# robot.net
KiCad netlist of a schematic drawn in EAGLE
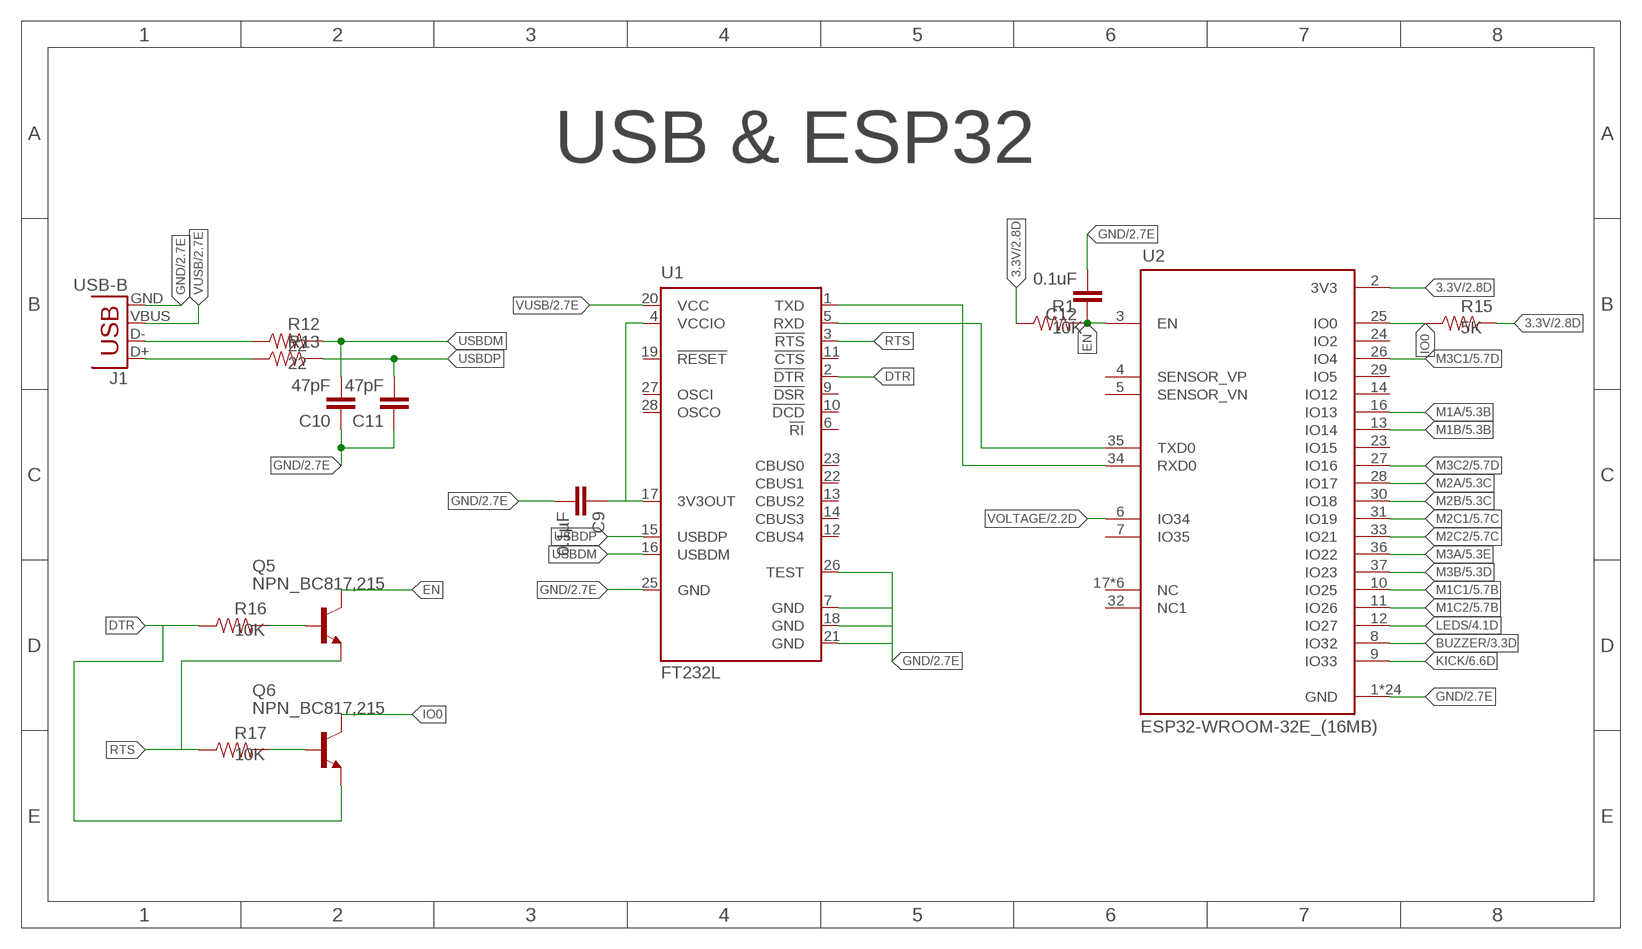
[diagram p0: schematic, sheet 1]
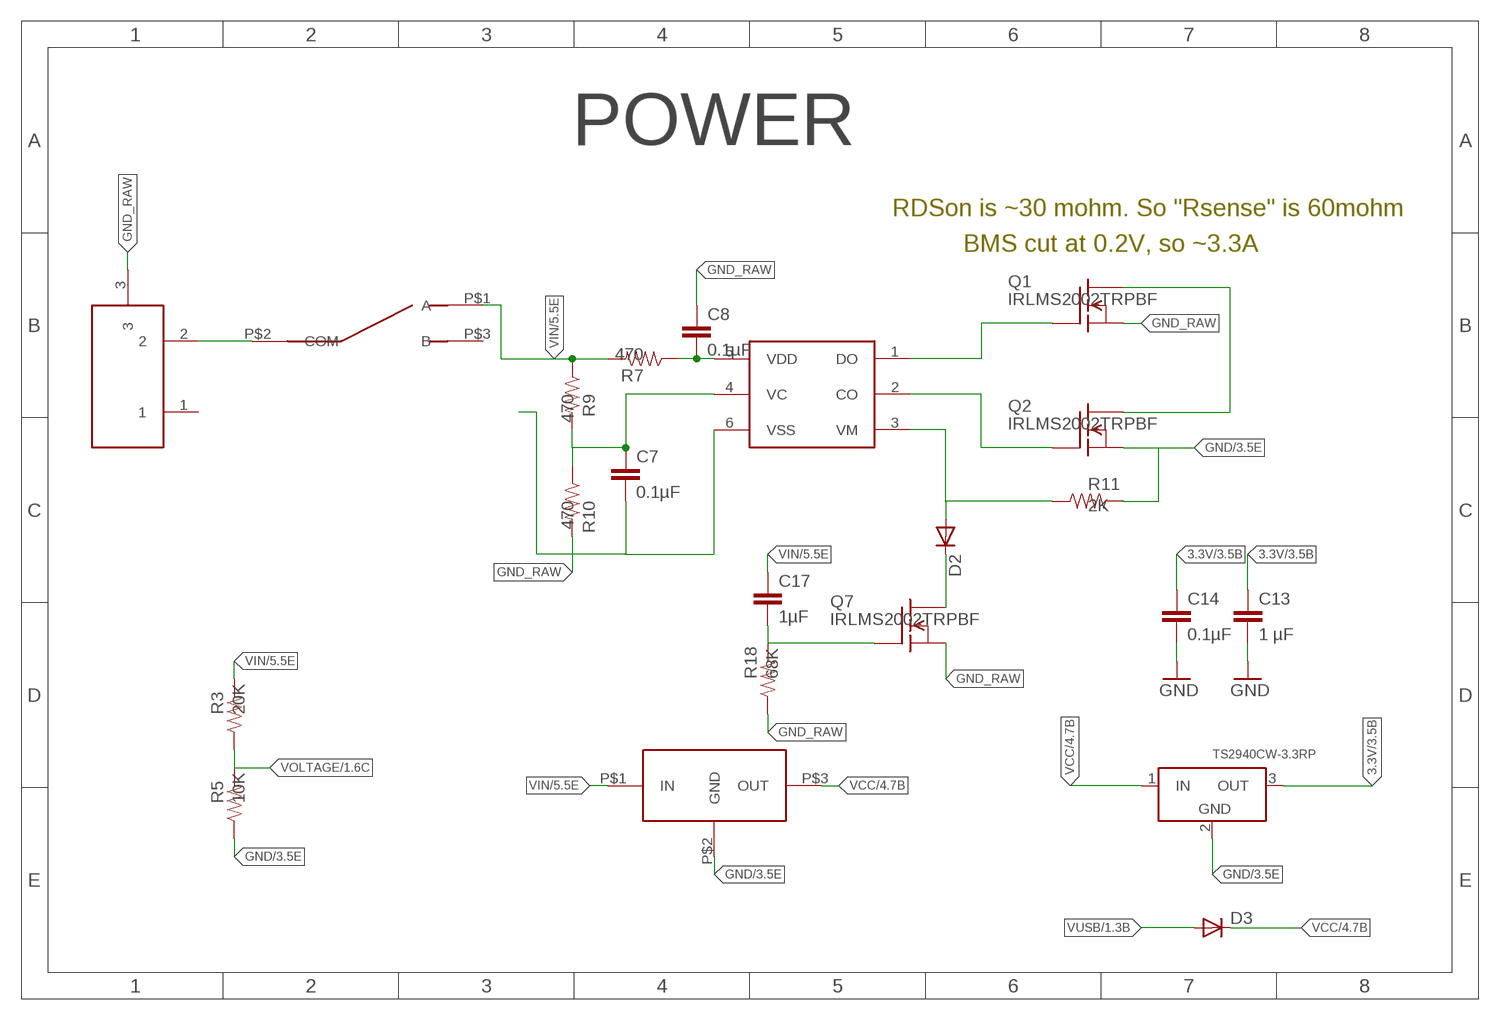
[diagram p1: schematic, sheet 2]
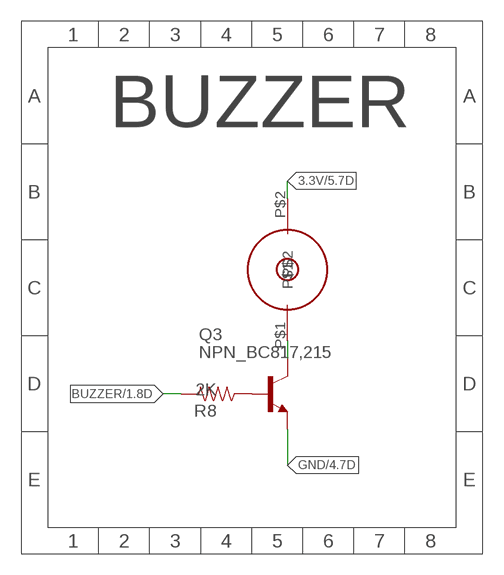
[diagram p2: schematic, sheet 3]
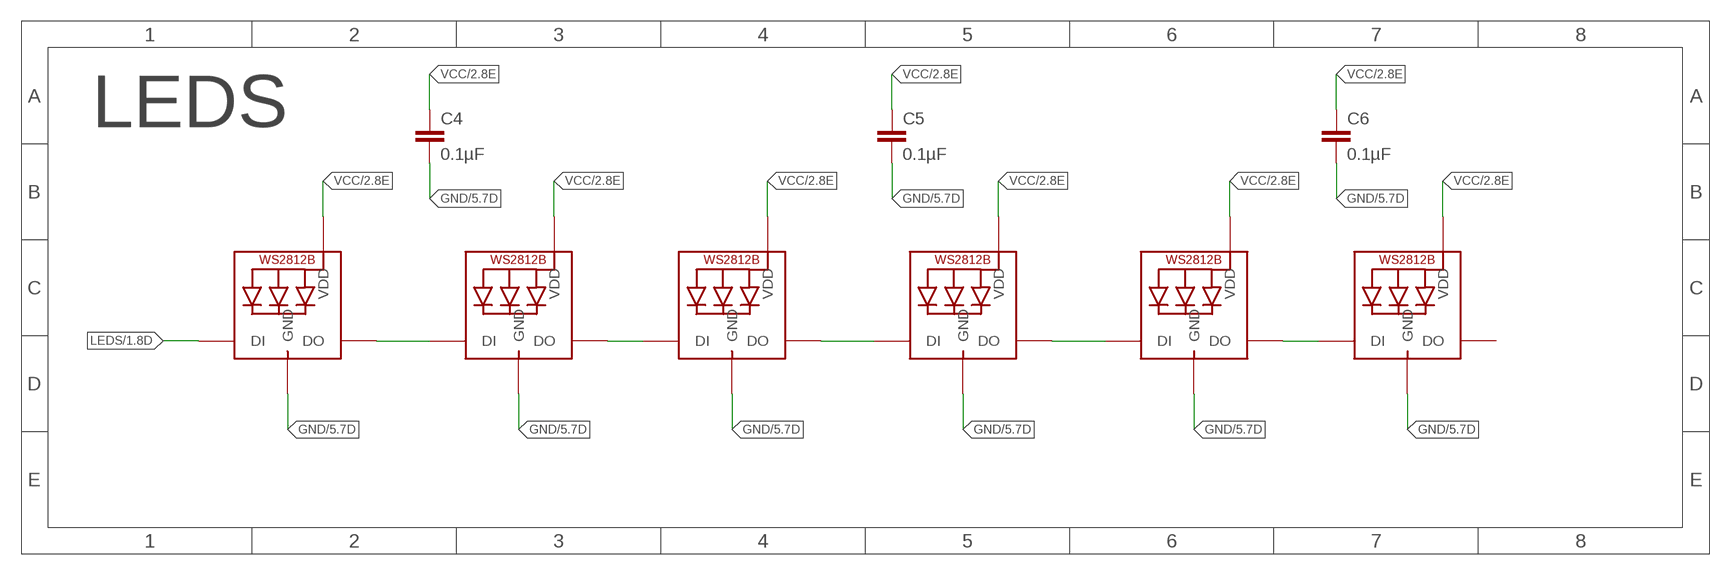
[diagram p3: schematic, sheet 4]
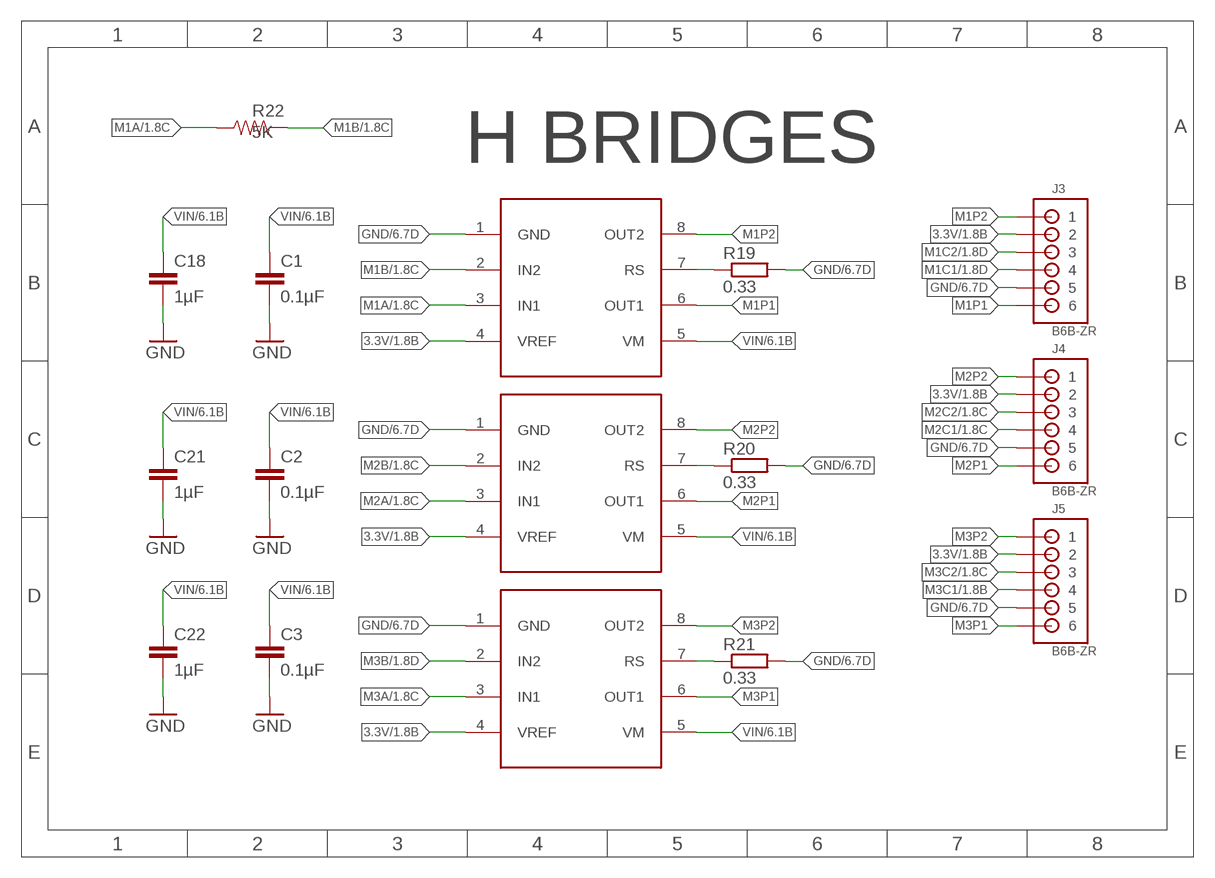
[diagram p4: schematic, sheet 5]
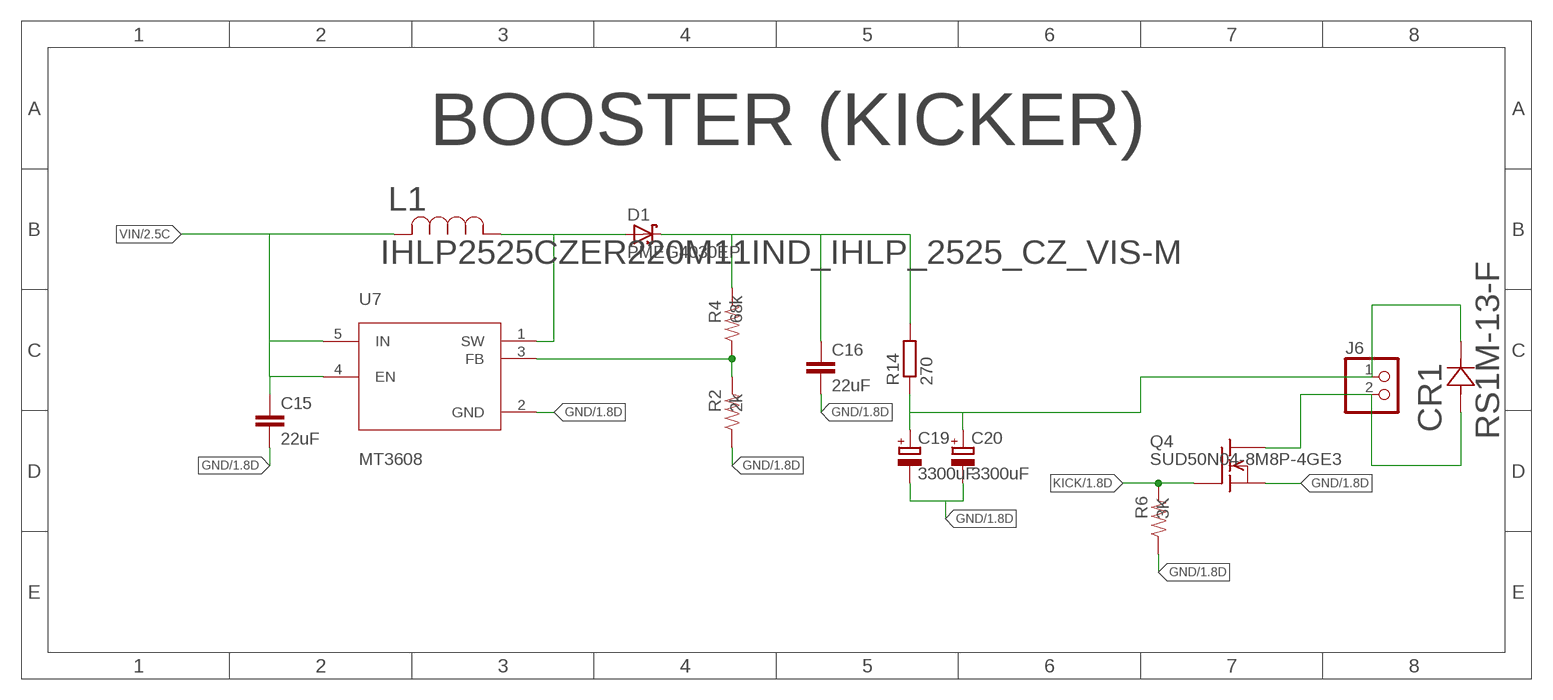
[diagram p5: schematic, sheet 6]

(export (version "E")
  (design (tool "Eeschema 10.0.6"))
  (components
    (comp (ref "C4")
      (value "0.1µF")
      (footprint "eagle-import:0805")
      (libsource (lib "eagle-import") (part "0.33UF/330NF-0805-50V-10%"))
    )
    (comp (ref "C5")
      (value "0.1µF")
      (footprint "eagle-import:0805")
      (fields (field (name "PROD_ID") "CAP-08469"))
      (libsource (lib "eagle-import") (part "0.33UF/330NF-0805-50V-10%"))
    )
    (comp (ref "C6")
      (value "0.1µF")
      (footprint "eagle-import:0805")
      (fields (field (name "PROD_ID") "CAP-08469"))
      (libsource (lib "eagle-import") (part "0.33UF/330NF-0805-50V-10%"))
    )
    (comp (ref "LED1")
      (value "WS2812B5050")
      (footprint "eagle-import:WS2812B")
      (libsource (lib "eagle-import") (part "WS2812B5050"))
    )
    (comp (ref "LED2")
      (value "WS2812B5050")
      (footprint "eagle-import:WS2812B")
      (libsource (lib "eagle-import") (part "WS2812B5050"))
    )
    (comp (ref "LED3")
      (value "WS2812B5050")
      (footprint "eagle-import:WS2812B")
      (libsource (lib "eagle-import") (part "WS2812B5050"))
    )
    (comp (ref "LED4")
      (value "WS2812B5050")
      (footprint "eagle-import:WS2812B")
      (libsource (lib "eagle-import") (part "WS2812B5050"))
    )
    (comp (ref "LED5")
      (value "WS2812B5050")
      (footprint "eagle-import:WS2812B")
      (libsource (lib "eagle-import") (part "WS2812B5050"))
    )
    (comp (ref "LED6")
      (value "WS2812B5050")
      (footprint "eagle-import:WS2812B")
      (libsource (lib "eagle-import") (part "WS2812B5050"))
    )
    (comp (ref "C9")
      (value "0.1µF")
      (footprint "eagle-import:0805")
      (libsource (lib "eagle-import") (part "0.33UF/330NF-0805-50V-10%"))
    )
    (comp (ref "C10")
      (value "47pF")
      (footprint "eagle-import:0805")
      (libsource (lib "eagle-import") (part "CAP0805"))
    )
    (comp (ref "C11")
      (value "47pF")
      (footprint "eagle-import:0805")
      (libsource (lib "eagle-import") (part "CAP0805"))
    )
    (comp (ref "C12")
      (value "0.1uF")
      (footprint "eagle-import:0805")
      (libsource (lib "eagle-import") (part "CAP0805"))
    )
    (comp (ref "J1")
      (value "USB-B")
      (footprint "eagle-import:USB-B-PTH")
      (libsource (lib "eagle-import") (part "USBPTH"))
    )
    (comp (ref "Q5")
      (value "NPN_BC817,215")
      (footprint "eagle-import:SOT-23")
      (libsource (lib "eagle-import") (part "NPN_BC817,215"))
    )
    (comp (ref "Q6")
      (value "NPN_BC817,215")
      (footprint "eagle-import:SOT-23")
      (libsource (lib "eagle-import") (part "NPN_BC817,215"))
    )
    (comp (ref "R1")
      (value "10K")
      (footprint "eagle-import:0805")
      (fields (field (name "PROD_ID") "RES-11622"))
      (libsource (lib "eagle-import") (part "0.3OHM-0805-1/8W-1%"))
    )
    (comp (ref "R12")
      (value "22")
      (footprint "eagle-import:0805")
      (libsource (lib "eagle-import") (part "0.3OHM-0805-1/8W-1%"))
    )
    (comp (ref "R13")
      (value "22")
      (footprint "eagle-import:0805")
      (fields (field (name "PROD_ID") "RES-11622"))
      (libsource (lib "eagle-import") (part "0.3OHM-0805-1/8W-1%"))
    )
    (comp (ref "R15")
      (value "5K")
      (footprint "eagle-import:0805")
      (fields (field (name "PROD_ID") "RES-11622"))
      (libsource (lib "eagle-import") (part "0.3OHM-0805-1/8W-1%"))
    )
    (comp (ref "R16")
      (value "10K")
      (footprint "eagle-import:0805")
      (fields (field (name "PROD_ID") "RES-11622"))
      (libsource (lib "eagle-import") (part "0.3OHM-0805-1/8W-1%"))
    )
    (comp (ref "R17")
      (value "10K")
      (footprint "eagle-import:0805")
      (fields (field (name "PROD_ID") "RES-11622"))
      (libsource (lib "eagle-import") (part "0.3OHM-0805-1/8W-1%"))
    )
    (comp (ref "U1")
      (value "FT232L")
      (footprint "eagle-import:SSOP28")
      (fields (field (name "MPN") "FT232RL"))
      (libsource (lib "eagle-import") (part "FT232L"))
    )
    (comp (ref "U2")
      (value "ESP32-WROOM-32E_(16MB)")
      (footprint "eagle-import:MODULE_ESP32-WROOM-32E_(16MB)")
      (fields (field (name "MF") "Espressif Systems") (field (name "MP") "ESP32-WROOM-32E (16MB)"))
      (libsource (lib "eagle-import") (part "ESP32-WROOM-32E_(16MB)"))
    )
    (comp (ref "C15")
      (value "22uF")
      (footprint "eagle-import:C0805")
      (libsource (lib "eagle-import") (part "C-EUC0805"))
    )
    (comp (ref "C16")
      (value "22uF")
      (footprint "eagle-import:C0805")
      (libsource (lib "eagle-import") (part "C-EUC0805"))
    )
    (comp (ref "C19")
      (value "3300uF")
      (footprint "eagle-import:E5-13")
      (libsource (lib "eagle-import") (part "CPOL-EUE5-13"))
    )
    (comp (ref "C20")
      (value "3300uF")
      (footprint "eagle-import:E5-13")
      (libsource (lib "eagle-import") (part "CPOL-EUE5-13"))
    )
    (comp (ref "CR1")
      (value "RS1M-13-F")
      (footprint "eagle-import:RS1M")
      (libsource (lib "eagle-import") (part "RS1M-13-F"))
    )
    (comp (ref "D1")
      (value "PMEG4030EP")
      (footprint "eagle-import:SOD128")
      (libsource (lib "eagle-import") (part "PMEG4030EP"))
    )
    (comp (ref "J6")
      (value "RHOBAN_KICKER")
      (footprint "eagle-import:RHOBAN_KICKER")
      (libsource (lib "eagle-import") (part "RHOBAN_KICKER"))
    )
    (comp (ref "L1")
      (value "IHLP2525CZER220M11IND_IHLP_2525_CZ_VIS-M")
      (footprint "eagle-import:IND_IHLP_2525_CZ_VIS-M")
      (fields (field (name "MANUFACTURER_PART_NUMBER") "IHLP2525CZER220M11"))
      (libsource (lib "eagle-import") (part "IHLP2525CZER220M11IND_IHLP_2525_CZ_VIS-M"))
    )
    (comp (ref "Q4")
      (value "SUD50N04-8M8P-4GE3")
      (footprint "eagle-import:TO252")
      (libsource (lib "eagle-import") (part "SUD50N04-8M8P-4GE3"))
    )
    (comp (ref "R2")
      (value "2k")
      (footprint "eagle-import:0805")
      (libsource (lib "eagle-import") (part "0.3OHM-0805-1/8W-1%"))
    )
    (comp (ref "R4")
      (value "68k")
      (footprint "eagle-import:0805")
      (libsource (lib "eagle-import") (part "0.3OHM-0805-1/8W-1%"))
    )
    (comp (ref "R6")
      (value "3K")
      (footprint "eagle-import:0805")
      (fields (field (name "PROD_ID") "RES-11622"))
      (libsource (lib "eagle-import") (part "0.3OHM-0805-1/8W-1%"))
    )
    (comp (ref "R14")
      (value "270")
      (footprint "eagle-import:R2010")
      (libsource (lib "eagle-import") (part "R-EU_R2010"))
    )
    (comp (ref "U7")
      (value "MT3608")
      (footprint "eagle-import:SOT95P280X145-6N")
      (fields (field (name "MF") "Aerosemi Technology Co., Ltd"))
      (libsource (lib "eagle-import") (part "MT3608"))
    )
    (comp (ref "C7")
      (value "0.1µF")
      (footprint "eagle-import:0805")
      (libsource (lib "eagle-import") (part "0.33UF/330NF-0805-50V-10%"))
    )
    (comp (ref "C8")
      (value "0.1µF")
      (footprint "eagle-import:0805")
      (fields (field (name "PROD_ID") "CAP-08469"))
      (libsource (lib "eagle-import") (part "0.33UF/330NF-0805-50V-10%"))
    )
    (comp (ref "C13")
      (value "1 µF")
      (footprint "eagle-import:0805")
      (fields (field (name "PROD_ID") "CAP-08469"))
      (libsource (lib "eagle-import") (part "0.33UF/330NF-0805-50V-10%"))
    )
    (comp (ref "C14")
      (value "0.1µF")
      (footprint "eagle-import:0805")
      (fields (field (name "PROD_ID") "CAP-08469"))
      (libsource (lib "eagle-import") (part "0.33UF/330NF-0805-50V-10%"))
    )
    (comp (ref "C17")
      (value "1µF")
      (footprint "eagle-import:0805")
      (fields (field (name "PROD_ID") "CAP-08469"))
      (libsource (lib "eagle-import") (part "0.33UF/330NF-0805-50V-10%"))
    )
    (comp (ref "D2")
      (value "DIODESOD")
      (footprint "eagle-import:SOD-323")
      (libsource (lib "eagle-import") (part "DIODESOD"))
    )
    (comp (ref "D3")
      (value "DIODESOD")
      (footprint "eagle-import:SOD-323")
      (libsource (lib "eagle-import") (part "DIODESOD"))
    )
    (comp (ref "J2")
      (value "DC21MMX")
      (footprint "eagle-import:DC-21MM")
      (libsource (lib "eagle-import") (part "DC21MMX"))
    )
    (comp (ref "Q1")
      (value "IRLMS2002TRPBF")
      (footprint "eagle-import:SOT23-6")
      (libsource (lib "eagle-import") (part "IRLMS2002TRPBF"))
    )
    (comp (ref "Q2")
      (value "IRLMS2002TRPBF")
      (footprint "eagle-import:SOT23-6")
      (libsource (lib "eagle-import") (part "IRLMS2002TRPBF"))
    )
    (comp (ref "Q7")
      (value "IRLMS2002TRPBF")
      (footprint "eagle-import:SOT23-6")
      (libsource (lib "eagle-import") (part "IRLMS2002TRPBF"))
    )
    (comp (ref "R3")
      (value "20K")
      (footprint "eagle-import:0805")
      (libsource (lib "eagle-import") (part "0.3OHM-0805-1/8W-1%"))
    )
    (comp (ref "R5")
      (value "10K")
      (footprint "eagle-import:0805")
      (libsource (lib "eagle-import") (part "0.3OHM-0805-1/8W-1%"))
    )
    (comp (ref "R7")
      (value "470")
      (footprint "eagle-import:0805")
      (libsource (lib "eagle-import") (part "0.3OHM-0805-1/8W-1%"))
    )
    (comp (ref "R9")
      (value "470")
      (footprint "eagle-import:0805")
      (libsource (lib "eagle-import") (part "0.3OHM-0805-1/8W-1%"))
    )
    (comp (ref "R10")
      (value "470")
      (footprint "eagle-import:0805")
      (libsource (lib "eagle-import") (part "0.3OHM-0805-1/8W-1%"))
    )
    (comp (ref "R11")
      (value "2K")
      (footprint "eagle-import:0805")
      (libsource (lib "eagle-import") (part "0.3OHM-0805-1/8W-1%"))
    )
    (comp (ref "R18")
      (value "68K")
      (footprint "eagle-import:0805")
      (fields (field (name "PROD_ID") "RES-11622"))
      (libsource (lib "eagle-import") (part "0.3OHM-0805-1/8W-1%"))
    )
    (comp (ref "REG1")
      (value "REG_5V")
      (footprint "eagle-import:TRACOPOWER")
      (libsource (lib "eagle-import") (part "REG_5V"))
    )
    (comp (ref "SW1")
      (value "L102011ML04Q")
      (footprint "eagle-import:L102011ML04Q")
      (libsource (lib "eagle-import") (part "L102011ML04Q"))
    )
    (comp (ref "U3")
      (value "S8252")
      (footprint "eagle-import:SOT23-6")
      (libsource (lib "eagle-import") (part "S8252"))
    )
    (comp (ref "U8")
      (value "TS2940CW-3.3RP")
      (footprint "eagle-import:SOT223")
      (libsource (lib "eagle-import") (part "TS2940CW-3.3RP"))
    )
    (comp (ref "B1")
      (value "BUZZER66")
      (footprint "eagle-import:BUZZER66")
      (libsource (lib "eagle-import") (part "BUZZER66"))
    )
    (comp (ref "Q3")
      (value "NPN_BC817,215")
      (footprint "eagle-import:SOT-23")
      (libsource (lib "eagle-import") (part "NPN_BC817,215"))
    )
    (comp (ref "R8")
      (value "2K")
      (footprint "eagle-import:0805")
      (libsource (lib "eagle-import") (part "0.3OHM-0805-1/8W-1%"))
    )
    (comp (ref "C1")
      (value "0.1µF")
      (footprint "eagle-import:0805")
      (libsource (lib "eagle-import") (part "0.33UF/330NF-0805-50V-10%"))
    )
    (comp (ref "C2")
      (value "0.1µF")
      (footprint "eagle-import:0805")
      (fields (field (name "PROD_ID") "CAP-08469"))
      (libsource (lib "eagle-import") (part "0.33UF/330NF-0805-50V-10%"))
    )
    (comp (ref "C3")
      (value "0.1µF")
      (footprint "eagle-import:0805")
      (fields (field (name "PROD_ID") "CAP-08469"))
      (libsource (lib "eagle-import") (part "0.33UF/330NF-0805-50V-10%"))
    )
    (comp (ref "C18")
      (value "1µF")
      (footprint "eagle-import:0805")
      (libsource (lib "eagle-import") (part "0.33UF/330NF-0805-50V-10%"))
    )
    (comp (ref "C21")
      (value "1µF")
      (footprint "eagle-import:0805")
      (fields (field (name "PROD_ID") "CAP-08469"))
      (libsource (lib "eagle-import") (part "0.33UF/330NF-0805-50V-10%"))
    )
    (comp (ref "C22")
      (value "1µF")
      (footprint "eagle-import:0805")
      (fields (field (name "PROD_ID") "CAP-08469"))
      (libsource (lib "eagle-import") (part "0.33UF/330NF-0805-50V-10%"))
    )
    (comp (ref "J3")
      (value "B6B-ZR")
      (footprint "eagle-import:B6B-ZR")
      (libsource (lib "eagle-import") (part "B6B-ZR"))
    )
    (comp (ref "J4")
      (value "B6B-ZR")
      (footprint "eagle-import:B6B-ZR")
      (libsource (lib "eagle-import") (part "B6B-ZR"))
    )
    (comp (ref "J5")
      (value "B6B-ZR")
      (footprint "eagle-import:B6B-ZR")
      (libsource (lib "eagle-import") (part "B6B-ZR"))
    )
    (comp (ref "R19")
      (value "0.33")
      (footprint "eagle-import:R1206")
      (libsource (lib "eagle-import") (part "R-EU_R1206"))
    )
    (comp (ref "R20")
      (value "0.33")
      (footprint "eagle-import:R1206")
      (libsource (lib "eagle-import") (part "R-EU_R1206"))
    )
    (comp (ref "R21")
      (value "0.33")
      (footprint "eagle-import:R1206")
      (libsource (lib "eagle-import") (part "R-EU_R1206"))
    )
    (comp (ref "R22")
      (value "5K")
      (footprint "eagle-import:0805")
      (fields (field (name "PROD_ID") "RES-11622"))
      (libsource (lib "eagle-import") (part "0.3OHM-0805-1/8W-1%"))
    )
    (comp (ref "U10")
      (value "TB67H450FNG")
      (footprint "eagle-import:HSOP8")
      (libsource (lib "eagle-import") (part "TB67H450FNG"))
    )
    (comp (ref "U11")
      (value "TB67H450FNG")
      (footprint "eagle-import:HSOP8")
      (libsource (lib "eagle-import") (part "TB67H450FNG"))
    )
    (comp (ref "U12")
      (value "TB67H450FNG")
      (footprint "eagle-import:HSOP8")
      (libsource (lib "eagle-import") (part "TB67H450FNG"))
    )
  )
  (nets
    (net (code "1") (name "1") (class "Default")
      (node (ref "J2") (pin "1") (pinfunction "1_1") (pintype "power_in"))
    )
    (net (code "2") (name "3.3V") (class "Default")
      (node (ref "B1") (pin "P$2") (pinfunction "P$2_P$2") (pintype "bidirectional"))
      (node (ref "C13") (pin "1") (pinfunction "1_1") (pintype "passive"))
      (node (ref "C14") (pin "1") (pinfunction "1_1") (pintype "passive"))
      (node (ref "J3") (pin "2") (pinfunction "2_2") (pintype "bidirectional"))
      (node (ref "J4") (pin "2") (pinfunction "2_2") (pintype "bidirectional"))
      (node (ref "J5") (pin "2") (pinfunction "2_2") (pintype "bidirectional"))
      (node (ref "R1") (pin "1") (pinfunction "1_1") (pintype "passive"))
      (node (ref "R15") (pin "2") (pinfunction "2_2") (pintype "passive"))
      (node (ref "U10") (pin "4") (pinfunction "VREF_4") (pintype "bidirectional"))
      (node (ref "U11") (pin "4") (pinfunction "VREF_4") (pintype "bidirectional"))
      (node (ref "U12") (pin "4") (pinfunction "VREF_4") (pintype "bidirectional"))
      (node (ref "U2") (pin "2") (pinfunction "3V3_2") (pintype "power_in"))
      (node (ref "U8") (pin "3") (pinfunction "OUT_3") (pintype "output"))
    )
    (net (code "3") (name "BUZZER") (class "Default")
      (node (ref "R8") (pin "2") (pinfunction "2_2") (pintype "passive"))
      (node (ref "U2") (pin "8") (pinfunction "IO32_8") (pintype "bidirectional"))
    )
    (net (code "4") (name "DTR") (class "Default")
      (node (ref "Q6") (pin "2") (pinfunction "E_2") (pintype "passive"))
      (node (ref "R16") (pin "1") (pinfunction "1_1") (pintype "passive"))
      (node (ref "U1") (pin "2") (pinfunction "~{DTR}_2") (pintype "output"))
    )
    (net (code "5") (name "EN") (class "Default")
      (node (ref "C12") (pin "1") (pinfunction "1_1") (pintype "passive"))
      (node (ref "Q5") (pin "3") (pinfunction "C_3") (pintype "passive"))
      (node (ref "R1") (pin "2") (pinfunction "2_2") (pintype "passive"))
      (node (ref "U2") (pin "3") (pinfunction "EN_3") (pintype "input"))
    )
    (net (code "6") (name "GND") (class "Default")
      (node (ref "C1") (pin "2") (pinfunction "2_2") (pintype "passive"))
      (node (ref "C10") (pin "1") (pinfunction "1_1") (pintype "passive"))
      (node (ref "C11") (pin "1") (pinfunction "1_1") (pintype "passive"))
      (node (ref "C12") (pin "2") (pinfunction "2_2") (pintype "passive"))
      (node (ref "C13") (pin "2") (pinfunction "2_2") (pintype "passive"))
      (node (ref "C14") (pin "2") (pinfunction "2_2") (pintype "passive"))
      (node (ref "C15") (pin "2") (pinfunction "2_2") (pintype "passive"))
      (node (ref "C16") (pin "2") (pinfunction "2_2") (pintype "passive"))
      (node (ref "C18") (pin "2") (pinfunction "2_2") (pintype "passive"))
      (node (ref "C19") (pin "-") (pinfunction "-_-") (pintype "passive"))
      (node (ref "C2") (pin "2") (pinfunction "2_2") (pintype "passive"))
      (node (ref "C20") (pin "-") (pinfunction "-_-") (pintype "passive"))
      (node (ref "C21") (pin "2") (pinfunction "2_2") (pintype "passive"))
      (node (ref "C22") (pin "2") (pinfunction "2_2") (pintype "passive"))
      (node (ref "C3") (pin "2") (pinfunction "2_2") (pintype "passive"))
      (node (ref "C4") (pin "2") (pinfunction "2_2") (pintype "passive"))
      (node (ref "C5") (pin "2") (pinfunction "2_2") (pintype "passive"))
      (node (ref "C6") (pin "2") (pinfunction "2_2") (pintype "passive"))
      (node (ref "C9") (pin "2") (pinfunction "2_2") (pintype "passive"))
      (node (ref "J1") (pin "GND") (pinfunction "GND_GND") (pintype "bidirectional"))
      (node (ref "J3") (pin "5") (pinfunction "5_5") (pintype "bidirectional"))
      (node (ref "J4") (pin "5") (pinfunction "5_5") (pintype "bidirectional"))
      (node (ref "J5") (pin "5") (pinfunction "5_5") (pintype "bidirectional"))
      (node (ref "LED1") (pin "3-GND") (pinfunction "GND_3-GND") (pintype "power_in"))
      (node (ref "LED2") (pin "3-GND") (pinfunction "GND_3-GND") (pintype "power_in"))
      (node (ref "LED3") (pin "3-GND") (pinfunction "GND_3-GND") (pintype "power_in"))
      (node (ref "LED4") (pin "3-GND") (pinfunction "GND_3-GND") (pintype "power_in"))
      (node (ref "LED5") (pin "3-GND") (pinfunction "GND_3-GND") (pintype "power_in"))
      (node (ref "LED6") (pin "3-GND") (pinfunction "GND_3-GND") (pintype "power_in"))
      (node (ref "Q2") (pin "4") (pinfunction "S_4") (pintype "passive"))
      (node (ref "Q3") (pin "2") (pinfunction "E_2") (pintype "passive"))
      (node (ref "Q4") (pin "2") (pinfunction "S_2") (pintype "passive"))
      (node (ref "R11") (pin "2") (pinfunction "2_2") (pintype "passive"))
      (node (ref "R19") (pin "2") (pinfunction "2_2") (pintype "passive"))
      (node (ref "R2") (pin "1") (pinfunction "1_1") (pintype "passive"))
      (node (ref "R20") (pin "2") (pinfunction "2_2") (pintype "passive"))
      (node (ref "R21") (pin "2") (pinfunction "2_2") (pintype "passive"))
      (node (ref "R5") (pin "1") (pinfunction "1_1") (pintype "passive"))
      (node (ref "R6") (pin "1") (pinfunction "1_1") (pintype "passive"))
      (node (ref "REG1") (pin "P$2") (pinfunction "GND_P$2") (pintype "bidirectional"))
      (node (ref "U1") (pin "18") (pinfunction "GND_18") (pintype "power_in"))
      (node (ref "U1") (pin "21") (pinfunction "GND_21") (pintype "power_in"))
      (node (ref "U1") (pin "25") (pinfunction "GND_25") (pintype "power_in"))
      (node (ref "U1") (pin "26") (pinfunction "TEST_26") (pintype "input"))
      (node (ref "U1") (pin "7") (pinfunction "GND_7") (pintype "power_in"))
      (node (ref "U10") (pin "1") (pinfunction "GND_1") (pintype "bidirectional"))
      (node (ref "U11") (pin "1") (pinfunction "GND_1") (pintype "bidirectional"))
      (node (ref "U12") (pin "1") (pinfunction "GND_1") (pintype "bidirectional"))
      (node (ref "U2") (pin "1") (pinfunction "GND_1") (pintype "power_in"))
      (node (ref "U2") (pin "15") (pinfunction "GND_15") (pintype "power_in"))
      (node (ref "U2") (pin "38") (pinfunction "GND_38") (pintype "power_in"))
      (node (ref "U2") (pin "39_1") (pinfunction "GND_39_1") (pintype "power_in"))
      (node (ref "U2") (pin "39_10") (pinfunction "GND_39_10") (pintype "power_in"))
      (node (ref "U2") (pin "39_11") (pinfunction "GND_39_11") (pintype "power_in"))
      (node (ref "U2") (pin "39_12") (pinfunction "GND_39_12") (pintype "power_in"))
      (node (ref "U2") (pin "39_13") (pinfunction "GND_39_13") (pintype "power_in"))
      (node (ref "U2") (pin "39_14") (pinfunction "GND_39_14") (pintype "power_in"))
      (node (ref "U2") (pin "39_15") (pinfunction "GND_39_15") (pintype "power_in"))
      (node (ref "U2") (pin "39_16") (pinfunction "GND_39_16") (pintype "power_in"))
      (node (ref "U2") (pin "39_17") (pinfunction "GND_39_17") (pintype "power_in"))
      (node (ref "U2") (pin "39_18") (pinfunction "GND_39_18") (pintype "power_in"))
      (node (ref "U2") (pin "39_19") (pinfunction "GND_39_19") (pintype "power_in"))
      (node (ref "U2") (pin "39_2") (pinfunction "GND_39_2") (pintype "power_in"))
      (node (ref "U2") (pin "39_20") (pinfunction "GND_39_20") (pintype "power_in"))
      (node (ref "U2") (pin "39_21") (pinfunction "GND_39_21") (pintype "power_in"))
      (node (ref "U2") (pin "39_3") (pinfunction "GND_39_3") (pintype "power_in"))
      (node (ref "U2") (pin "39_4") (pinfunction "GND_39_4") (pintype "power_in"))
      (node (ref "U2") (pin "39_5") (pinfunction "GND_39_5") (pintype "power_in"))
      (node (ref "U2") (pin "39_6") (pinfunction "GND_39_6") (pintype "power_in"))
      (node (ref "U2") (pin "39_7") (pinfunction "GND_39_7") (pintype "power_in"))
      (node (ref "U2") (pin "39_8") (pinfunction "GND_39_8") (pintype "power_in"))
      (node (ref "U2") (pin "39_9") (pinfunction "GND_39_9") (pintype "power_in"))
      (node (ref "U7") (pin "2") (pinfunction "GND_2") (pintype "power_in"))
      (node (ref "U8") (pin "2") (pinfunction "GND_2") (pintype "power_in"))
    )
    (net (code "7") (name "GND_RAW") (class "Default")
      (node (ref "C7") (pin "2") (pinfunction "2_2") (pintype "passive"))
      (node (ref "C8") (pin "1") (pinfunction "1_1") (pintype "passive"))
      (node (ref "J2") (pin "3") (pinfunction "3_3") (pintype "power_in"))
      (node (ref "Q1") (pin "4") (pinfunction "S_4") (pintype "passive"))
      (node (ref "Q7") (pin "4") (pinfunction "S_4") (pintype "passive"))
      (node (ref "R10") (pin "2") (pinfunction "2_2") (pintype "passive"))
      (node (ref "R18") (pin "1") (pinfunction "1_1") (pintype "passive"))
      (node (ref "U3") (pin "6") (pinfunction "VSS_6") (pintype "passive"))
    )
    (net (code "8") (name "IO0") (class "Default")
      (node (ref "Q6") (pin "3") (pinfunction "C_3") (pintype "passive"))
      (node (ref "R15") (pin "1") (pinfunction "1_1") (pintype "passive"))
      (node (ref "U2") (pin "25") (pinfunction "IO0_25") (pintype "bidirectional"))
    )
    (net (code "9") (name "KICK") (class "Default")
      (node (ref "Q4") (pin "1") (pinfunction "G_1") (pintype "passive"))
      (node (ref "R6") (pin "2") (pinfunction "2_2") (pintype "passive"))
      (node (ref "U2") (pin "9") (pinfunction "IO33_9") (pintype "bidirectional"))
    )
    (net (code "10") (name "LEDS") (class "Default")
      (node (ref "LED1") (pin "4-DIN") (pinfunction "DI_4-DIN") (pintype "input"))
      (node (ref "U2") (pin "12") (pinfunction "IO27_12") (pintype "bidirectional"))
    )
    (net (code "11") (name "M1A") (class "Default")
      (node (ref "R22") (pin "1") (pinfunction "1_1") (pintype "passive"))
      (node (ref "U10") (pin "3") (pinfunction "IN1_3") (pintype "bidirectional"))
      (node (ref "U2") (pin "16") (pinfunction "IO13_16") (pintype "bidirectional"))
    )
    (net (code "12") (name "M1B") (class "Default")
      (node (ref "R22") (pin "2") (pinfunction "2_2") (pintype "passive"))
      (node (ref "U10") (pin "2") (pinfunction "IN2_2") (pintype "bidirectional"))
      (node (ref "U2") (pin "13") (pinfunction "IO14_13") (pintype "bidirectional"))
    )
    (net (code "13") (name "M1C1") (class "Default")
      (node (ref "J3") (pin "4") (pinfunction "4_4") (pintype "bidirectional"))
      (node (ref "U2") (pin "10") (pinfunction "IO25_10") (pintype "bidirectional"))
    )
    (net (code "14") (name "M1C2") (class "Default")
      (node (ref "J3") (pin "3") (pinfunction "3_3") (pintype "bidirectional"))
      (node (ref "U2") (pin "11") (pinfunction "IO26_11") (pintype "bidirectional"))
    )
    (net (code "15") (name "M1P1") (class "Default")
      (node (ref "J3") (pin "6") (pinfunction "6_6") (pintype "bidirectional"))
      (node (ref "U10") (pin "6") (pinfunction "OUT1_6") (pintype "bidirectional"))
    )
    (net (code "16") (name "M1P2") (class "Default")
      (node (ref "J3") (pin "1") (pinfunction "1_1") (pintype "bidirectional"))
      (node (ref "U10") (pin "8") (pinfunction "OUT2_8") (pintype "bidirectional"))
    )
    (net (code "17") (name "M2A") (class "Default")
      (node (ref "U11") (pin "3") (pinfunction "IN1_3") (pintype "bidirectional"))
      (node (ref "U2") (pin "28") (pinfunction "IO17_28") (pintype "bidirectional"))
    )
    (net (code "18") (name "M2B") (class "Default")
      (node (ref "U11") (pin "2") (pinfunction "IN2_2") (pintype "bidirectional"))
      (node (ref "U2") (pin "30") (pinfunction "IO18_30") (pintype "bidirectional"))
    )
    (net (code "19") (name "M2C1") (class "Default")
      (node (ref "J4") (pin "4") (pinfunction "4_4") (pintype "bidirectional"))
      (node (ref "U2") (pin "31") (pinfunction "IO19_31") (pintype "bidirectional"))
    )
    (net (code "20") (name "M2C2") (class "Default")
      (node (ref "J4") (pin "3") (pinfunction "3_3") (pintype "bidirectional"))
      (node (ref "U2") (pin "33") (pinfunction "IO21_33") (pintype "bidirectional"))
    )
    (net (code "21") (name "M2P1") (class "Default")
      (node (ref "J4") (pin "6") (pinfunction "6_6") (pintype "bidirectional"))
      (node (ref "U11") (pin "6") (pinfunction "OUT1_6") (pintype "bidirectional"))
    )
    (net (code "22") (name "M2P2") (class "Default")
      (node (ref "J4") (pin "1") (pinfunction "1_1") (pintype "bidirectional"))
      (node (ref "U11") (pin "8") (pinfunction "OUT2_8") (pintype "bidirectional"))
    )
    (net (code "23") (name "M3A") (class "Default")
      (node (ref "U12") (pin "3") (pinfunction "IN1_3") (pintype "bidirectional"))
      (node (ref "U2") (pin "36") (pinfunction "IO22_36") (pintype "bidirectional"))
    )
    (net (code "24") (name "M3B") (class "Default")
      (node (ref "U12") (pin "2") (pinfunction "IN2_2") (pintype "bidirectional"))
      (node (ref "U2") (pin "37") (pinfunction "IO23_37") (pintype "bidirectional"))
    )
    (net (code "25") (name "M3C1") (class "Default")
      (node (ref "J5") (pin "4") (pinfunction "4_4") (pintype "bidirectional"))
      (node (ref "U2") (pin "26") (pinfunction "IO4_26") (pintype "bidirectional"))
    )
    (net (code "26") (name "M3C2") (class "Default")
      (node (ref "J5") (pin "3") (pinfunction "3_3") (pintype "bidirectional"))
      (node (ref "U2") (pin "27") (pinfunction "IO16_27") (pintype "bidirectional"))
    )
    (net (code "27") (name "M3P1") (class "Default")
      (node (ref "J5") (pin "6") (pinfunction "6_6") (pintype "bidirectional"))
      (node (ref "U12") (pin "6") (pinfunction "OUT1_6") (pintype "bidirectional"))
    )
    (net (code "28") (name "M3P2") (class "Default")
      (node (ref "J5") (pin "1") (pinfunction "1_1") (pintype "bidirectional"))
      (node (ref "U12") (pin "8") (pinfunction "OUT2_8") (pintype "bidirectional"))
    )
    (net (code "29") (name "Net-(C19-Pad+)") (class "Default")
      (node (ref "C19") (pin "+") (pinfunction "+_+") (pintype "passive"))
      (node (ref "C20") (pin "+") (pinfunction "+_+") (pintype "passive"))
      (node (ref "CR1") (pin "K") (pinfunction "K_K") (pintype "passive"))
      (node (ref "J6") (pin "1") (pinfunction "1_1") (pintype "passive"))
      (node (ref "R14") (pin "1") (pinfunction "1_1") (pintype "passive"))
    )
    (net (code "30") (name "Net-(D1-A)") (class "Default")
      (node (ref "D1") (pin "2") (pinfunction "A_2") (pintype "passive"))
      (node (ref "L1") (pin "1") (pinfunction "1_1") (pintype "passive"))
      (node (ref "U7") (pin "1") (pinfunction "SW_1") (pintype "output"))
    )
    (net (code "31") (name "Net-(D1-K)") (class "Default")
      (node (ref "C16") (pin "1") (pinfunction "1_1") (pintype "passive"))
      (node (ref "D1") (pin "1") (pinfunction "K_1") (pintype "passive"))
      (node (ref "R14") (pin "2") (pinfunction "2_2") (pintype "passive"))
      (node (ref "R4") (pin "2") (pinfunction "2_2") (pintype "passive"))
    )
    (net (code "32") (name "Net-(D2-A)") (class "Default")
      (node (ref "D2") (pin "2") (pinfunction "A_2") (pintype "passive"))
      (node (ref "R11") (pin "1") (pinfunction "1_1") (pintype "passive"))
      (node (ref "U3") (pin "3") (pinfunction "VM_3") (pintype "passive"))
    )
    (net (code "33") (name "Net-(D2-C)") (class "Default")
      (node (ref "D2") (pin "1") (pinfunction "C_1") (pintype "passive"))
      (node (ref "Q7") (pin "1") (pinfunction "D_1") (pintype "passive"))
      (node (ref "Q7") (pin "2") (pinfunction "D_2") (pintype "passive"))
      (node (ref "Q7") (pin "5") (pinfunction "D_5") (pintype "passive"))
      (node (ref "Q7") (pin "6") (pinfunction "D_6") (pintype "passive"))
    )
    (net (code "34") (name "Net-(J1-PadD+)") (class "Default")
      (node (ref "J1") (pin "D+") (pinfunction "D+_D+") (pintype "bidirectional"))
      (node (ref "R13") (pin "1") (pinfunction "1_1") (pintype "passive"))
    )
    (net (code "35") (name "Net-(J1-PadD-)") (class "Default")
      (node (ref "J1") (pin "D-") (pinfunction "D-_D-") (pintype "bidirectional"))
      (node (ref "R12") (pin "1") (pinfunction "1_1") (pintype "passive"))
    )
    (net (code "36") (name "Net-(LED1-DO)") (class "Default")
      (node (ref "LED1") (pin "2-DOUT") (pinfunction "DO_2-DOUT") (pintype "output"))
      (node (ref "LED2") (pin "4-DIN") (pinfunction "DI_4-DIN") (pintype "input"))
    )
    (net (code "37") (name "Net-(LED2-DO)") (class "Default")
      (node (ref "LED2") (pin "2-DOUT") (pinfunction "DO_2-DOUT") (pintype "output"))
      (node (ref "LED3") (pin "4-DIN") (pinfunction "DI_4-DIN") (pintype "input"))
    )
    (net (code "38") (name "Net-(LED3-DO)") (class "Default")
      (node (ref "LED3") (pin "2-DOUT") (pinfunction "DO_2-DOUT") (pintype "output"))
      (node (ref "LED4") (pin "4-DIN") (pinfunction "DI_4-DIN") (pintype "input"))
    )
    (net (code "39") (name "Net-(LED4-DO)") (class "Default")
      (node (ref "LED4") (pin "2-DOUT") (pinfunction "DO_2-DOUT") (pintype "output"))
      (node (ref "LED5") (pin "4-DIN") (pinfunction "DI_4-DIN") (pintype "input"))
    )
    (net (code "40") (name "Net-(LED5-DO)") (class "Default")
      (node (ref "LED5") (pin "2-DOUT") (pinfunction "DO_2-DOUT") (pintype "output"))
      (node (ref "LED6") (pin "4-DIN") (pinfunction "DI_4-DIN") (pintype "input"))
    )
    (net (code "41") (name "Net-(Q1-D-Pad1)") (class "Default")
      (node (ref "Q1") (pin "1") (pinfunction "D_1") (pintype "passive"))
      (node (ref "Q1") (pin "2") (pinfunction "D_2") (pintype "passive"))
      (node (ref "Q1") (pin "5") (pinfunction "D_5") (pintype "passive"))
      (node (ref "Q1") (pin "6") (pinfunction "D_6") (pintype "passive"))
      (node (ref "Q2") (pin "1") (pinfunction "D_1") (pintype "passive"))
      (node (ref "Q2") (pin "2") (pinfunction "D_2") (pintype "passive"))
      (node (ref "Q2") (pin "5") (pinfunction "D_5") (pintype "passive"))
      (node (ref "Q2") (pin "6") (pinfunction "D_6") (pintype "passive"))
    )
    (net (code "42") (name "Net-(Q1-G)") (class "Default")
      (node (ref "Q1") (pin "3") (pinfunction "G_3") (pintype "passive"))
      (node (ref "U3") (pin "1") (pinfunction "DO_1") (pintype "passive"))
    )
    (net (code "43") (name "Net-(Q2-G)") (class "Default")
      (node (ref "Q2") (pin "3") (pinfunction "G_3") (pintype "passive"))
      (node (ref "U3") (pin "2") (pinfunction "CO_2") (pintype "passive"))
    )
    (net (code "44") (name "Net-(Q3-B)") (class "Default")
      (node (ref "Q3") (pin "1") (pinfunction "B_1") (pintype "passive"))
      (node (ref "R8") (pin "1") (pinfunction "1_1") (pintype "passive"))
    )
    (net (code "45") (name "Net-(Q3-C)") (class "Default")
      (node (ref "B1") (pin "P$1") (pinfunction "P$1_P$1") (pintype "bidirectional"))
      (node (ref "Q3") (pin "3") (pinfunction "C_3") (pintype "passive"))
    )
    (net (code "46") (name "Net-(Q4-D)") (class "Default")
      (node (ref "CR1") (pin "A") (pinfunction "A_A") (pintype "passive"))
      (node (ref "J6") (pin "2") (pinfunction "2_2") (pintype "passive"))
      (node (ref "Q4") (pin "3") (pinfunction "D_3") (pintype "passive"))
    )
    (net (code "47") (name "Net-(Q5-B)") (class "Default")
      (node (ref "Q5") (pin "1") (pinfunction "B_1") (pintype "passive"))
      (node (ref "R16") (pin "2") (pinfunction "2_2") (pintype "passive"))
    )
    (net (code "48") (name "Net-(Q6-B)") (class "Default")
      (node (ref "Q6") (pin "1") (pinfunction "B_1") (pintype "passive"))
      (node (ref "R17") (pin "2") (pinfunction "2_2") (pintype "passive"))
    )
    (net (code "49") (name "Net-(Q7-G)") (class "Default")
      (node (ref "C17") (pin "2") (pinfunction "2_2") (pintype "passive"))
      (node (ref "Q7") (pin "3") (pinfunction "G_3") (pintype "passive"))
      (node (ref "R18") (pin "2") (pinfunction "2_2") (pintype "passive"))
    )
    (net (code "50") (name "Net-(SW1-COM)") (class "Default")
      (node (ref "J2") (pin "2") (pinfunction "2_2") (pintype "power_in"))
      (node (ref "SW1") (pin "P$2") (pinfunction "COM_P$2") (pintype "bidirectional"))
    )
    (net (code "51") (name "Net-(U1-3V3OUT)") (class "Default")
      (node (ref "C9") (pin "1") (pinfunction "1_1") (pintype "passive"))
      (node (ref "U1") (pin "17") (pinfunction "3V3OUT_17") (pintype "output"))
      (node (ref "U1") (pin "4") (pinfunction "VCCIO_4") (pintype "power_in"))
    )
    (net (code "52") (name "Net-(U1-RXD)") (class "Default")
      (node (ref "U1") (pin "5") (pinfunction "RXD_5") (pintype "input"))
      (node (ref "U2") (pin "35") (pinfunction "TXD0_35") (pintype "bidirectional"))
    )
    (net (code "53") (name "Net-(U1-TXD)") (class "Default")
      (node (ref "U1") (pin "1") (pinfunction "TXD_1") (pintype "output"))
      (node (ref "U2") (pin "34") (pinfunction "RXD0_34") (pintype "bidirectional"))
    )
    (net (code "54") (name "Net-(U3-VC)") (class "Default")
      (node (ref "C7") (pin "1") (pinfunction "1_1") (pintype "passive"))
      (node (ref "R10") (pin "1") (pinfunction "1_1") (pintype "passive"))
      (node (ref "R9") (pin "2") (pinfunction "2_2") (pintype "passive"))
      (node (ref "U3") (pin "4") (pinfunction "VC_4") (pintype "passive"))
    )
    (net (code "55") (name "Net-(U3-VDD)") (class "Default")
      (node (ref "C8") (pin "2") (pinfunction "2_2") (pintype "passive"))
      (node (ref "R7") (pin "1") (pinfunction "1_1") (pintype "passive"))
      (node (ref "U3") (pin "5") (pinfunction "VDD_5") (pintype "passive"))
    )
    (net (code "56") (name "Net-(U7-FB)") (class "Default")
      (node (ref "R2") (pin "2") (pinfunction "2_2") (pintype "passive"))
      (node (ref "R4") (pin "1") (pinfunction "1_1") (pintype "passive"))
      (node (ref "U7") (pin "3") (pinfunction "FB_3") (pintype "input"))
    )
    (net (code "57") (name "Net-(U10-RS)") (class "Default")
      (node (ref "R19") (pin "1") (pinfunction "1_1") (pintype "passive"))
      (node (ref "U10") (pin "7") (pinfunction "RS_7") (pintype "bidirectional"))
    )
    (net (code "58") (name "Net-(U11-RS)") (class "Default")
      (node (ref "R20") (pin "1") (pinfunction "1_1") (pintype "passive"))
      (node (ref "U11") (pin "7") (pinfunction "RS_7") (pintype "bidirectional"))
    )
    (net (code "59") (name "Net-(U12-RS)") (class "Default")
      (node (ref "R21") (pin "1") (pinfunction "1_1") (pintype "passive"))
      (node (ref "U12") (pin "7") (pinfunction "RS_7") (pintype "bidirectional"))
    )
    (net (code "60") (name "RTS") (class "Default")
      (node (ref "Q5") (pin "2") (pinfunction "E_2") (pintype "passive"))
      (node (ref "R17") (pin "1") (pinfunction "1_1") (pintype "passive"))
      (node (ref "U1") (pin "3") (pinfunction "~{RTS}_3") (pintype "output"))
    )
    (net (code "61") (name "USBDM") (class "Default")
      (node (ref "C10") (pin "2") (pinfunction "2_2") (pintype "passive"))
      (node (ref "R12") (pin "2") (pinfunction "2_2") (pintype "passive"))
      (node (ref "U1") (pin "16") (pinfunction "USBDM_16") (pintype "bidirectional"))
    )
    (net (code "62") (name "USBDP") (class "Default")
      (node (ref "C11") (pin "2") (pinfunction "2_2") (pintype "passive"))
      (node (ref "R13") (pin "2") (pinfunction "2_2") (pintype "passive"))
      (node (ref "U1") (pin "15") (pinfunction "USBDP_15") (pintype "bidirectional"))
    )
    (net (code "63") (name "VCC") (class "Default")
      (node (ref "C4") (pin "1") (pinfunction "1_1") (pintype "passive"))
      (node (ref "C5") (pin "1") (pinfunction "1_1") (pintype "passive"))
      (node (ref "C6") (pin "1") (pinfunction "1_1") (pintype "passive"))
      (node (ref "D3") (pin "1") (pinfunction "C_1") (pintype "passive"))
      (node (ref "LED1") (pin "1-VDD") (pinfunction "VDD_1-VDD") (pintype "power_in"))
      (node (ref "LED2") (pin "1-VDD") (pinfunction "VDD_1-VDD") (pintype "power_in"))
      (node (ref "LED3") (pin "1-VDD") (pinfunction "VDD_1-VDD") (pintype "power_in"))
      (node (ref "LED4") (pin "1-VDD") (pinfunction "VDD_1-VDD") (pintype "power_in"))
      (node (ref "LED5") (pin "1-VDD") (pinfunction "VDD_1-VDD") (pintype "power_in"))
      (node (ref "LED6") (pin "1-VDD") (pinfunction "VDD_1-VDD") (pintype "power_in"))
      (node (ref "REG1") (pin "P$3") (pinfunction "OUT_P$3") (pintype "bidirectional"))
      (node (ref "U8") (pin "1") (pinfunction "IN_1") (pintype "input"))
    )
    (net (code "64") (name "VIN") (class "Default")
      (node (ref "C1") (pin "1") (pinfunction "1_1") (pintype "passive"))
      (node (ref "C15") (pin "1") (pinfunction "1_1") (pintype "passive"))
      (node (ref "C17") (pin "1") (pinfunction "1_1") (pintype "passive"))
      (node (ref "C18") (pin "1") (pinfunction "1_1") (pintype "passive"))
      (node (ref "C2") (pin "1") (pinfunction "1_1") (pintype "passive"))
      (node (ref "C21") (pin "1") (pinfunction "1_1") (pintype "passive"))
      (node (ref "C22") (pin "1") (pinfunction "1_1") (pintype "passive"))
      (node (ref "C3") (pin "1") (pinfunction "1_1") (pintype "passive"))
      (node (ref "L1") (pin "2") (pinfunction "2_2") (pintype "passive"))
      (node (ref "R3") (pin "2") (pinfunction "2_2") (pintype "passive"))
      (node (ref "R7") (pin "2") (pinfunction "2_2") (pintype "passive"))
      (node (ref "R9") (pin "1") (pinfunction "1_1") (pintype "passive"))
      (node (ref "REG1") (pin "P$1") (pinfunction "IN_P$1") (pintype "bidirectional"))
      (node (ref "SW1") (pin "P$1") (pinfunction "A_P$1") (pintype "bidirectional"))
      (node (ref "U10") (pin "5") (pinfunction "VM_5") (pintype "bidirectional"))
      (node (ref "U11") (pin "5") (pinfunction "VM_5") (pintype "bidirectional"))
      (node (ref "U12") (pin "5") (pinfunction "VM_5") (pintype "bidirectional"))
      (node (ref "U7") (pin "4") (pinfunction "EN_4") (pintype "input"))
      (node (ref "U7") (pin "5") (pinfunction "IN_5") (pintype "input"))
    )
    (net (code "65") (name "VOLTAGE") (class "Default")
      (node (ref "R3") (pin "1") (pinfunction "1_1") (pintype "passive"))
      (node (ref "R5") (pin "2") (pinfunction "2_2") (pintype "passive"))
      (node (ref "U2") (pin "6") (pinfunction "IO34_6") (pintype "input"))
    )
    (net (code "66") (name "VUSB") (class "Default")
      (node (ref "D3") (pin "2") (pinfunction "A_2") (pintype "passive"))
      (node (ref "J1") (pin "VBUS") (pinfunction "VBUS_VBUS") (pintype "bidirectional"))
      (node (ref "U1") (pin "20") (pinfunction "VCC_20") (pintype "power_in"))
    )
    (net (code "67") (name "unconnected-(LED6-DO-Pad2-DOUT)") (class "Default")
      (node (ref "LED6") (pin "2-DOUT") (pinfunction "DO_2-DOUT") (pintype "output"))
    )
    (net (code "68") (name "unconnected-(SW1-B-PadP$3)") (class "Default")
      (node (ref "SW1") (pin "P$3") (pinfunction "B_P$3") (pintype "bidirectional"))
    )
    (net (code "69") (name "unconnected-(U1-CBUS0-Pad23)") (class "Default")
      (node (ref "U1") (pin "23") (pinfunction "CBUS0_23") (pintype "bidirectional"))
    )
    (net (code "70") (name "unconnected-(U1-CBUS1-Pad22)") (class "Default")
      (node (ref "U1") (pin "22") (pinfunction "CBUS1_22") (pintype "bidirectional"))
    )
    (net (code "71") (name "unconnected-(U1-CBUS2-Pad13)") (class "Default")
      (node (ref "U1") (pin "13") (pinfunction "CBUS2_13") (pintype "bidirectional"))
    )
    (net (code "72") (name "unconnected-(U1-CBUS3-Pad14)") (class "Default")
      (node (ref "U1") (pin "14") (pinfunction "CBUS3_14") (pintype "bidirectional"))
    )
    (net (code "73") (name "unconnected-(U1-CBUS4-Pad12)") (class "Default")
      (node (ref "U1") (pin "12") (pinfunction "CBUS4_12") (pintype "bidirectional"))
    )
    (net (code "74") (name "unconnected-(U1-OSCI-Pad27)") (class "Default")
      (node (ref "U1") (pin "27") (pinfunction "OSCI_27") (pintype "input"))
    )
    (net (code "75") (name "unconnected-(U1-OSCO-Pad28)") (class "Default")
      (node (ref "U1") (pin "28") (pinfunction "OSCO_28") (pintype "output"))
    )
    (net (code "76") (name "unconnected-(U1-~{CTS}-Pad11)") (class "Default")
      (node (ref "U1") (pin "11") (pinfunction "~{CTS}_11") (pintype "input"))
    )
    (net (code "77") (name "unconnected-(U1-~{DCD}-Pad10)") (class "Default")
      (node (ref "U1") (pin "10") (pinfunction "~{DCD}_10") (pintype "input"))
    )
    (net (code "78") (name "unconnected-(U1-~{DSR}-Pad9)") (class "Default")
      (node (ref "U1") (pin "9") (pinfunction "~{DSR}_9") (pintype "input"))
    )
    (net (code "79") (name "unconnected-(U1-~{RESET}-Pad19)") (class "Default")
      (node (ref "U1") (pin "19") (pinfunction "~{RESET}_19") (pintype "input"))
    )
    (net (code "80") (name "unconnected-(U1-~{RI}-Pad6)") (class "Default")
      (node (ref "U1") (pin "6") (pinfunction "~{RI}_6") (pintype "input"))
    )
    (net (code "81") (name "unconnected-(U2-IO2-Pad24)") (class "Default")
      (node (ref "U2") (pin "24") (pinfunction "IO2_24") (pintype "bidirectional"))
    )
    (net (code "82") (name "unconnected-(U2-IO5-Pad29)") (class "Default")
      (node (ref "U2") (pin "29") (pinfunction "IO5_29") (pintype "bidirectional"))
    )
    (net (code "83") (name "unconnected-(U2-IO12-Pad14)") (class "Default")
      (node (ref "U2") (pin "14") (pinfunction "IO12_14") (pintype "bidirectional"))
    )
    (net (code "84") (name "unconnected-(U2-IO15-Pad23)") (class "Default")
      (node (ref "U2") (pin "23") (pinfunction "IO15_23") (pintype "bidirectional"))
    )
    (net (code "85") (name "unconnected-(U2-IO35-Pad7)") (class "Default")
      (node (ref "U2") (pin "7") (pinfunction "IO35_7") (pintype "input"))
    )
    (net (code "86") (name "unconnected-(U2-NC-Pad17)") (class "Default")
      (node (ref "U2") (pin "17") (pinfunction "NC_17") (pintype "no_connect"))
    )
    (net (code "87") (name "unconnected-(U2-NC-Pad18)") (class "Default")
      (node (ref "U2") (pin "18") (pinfunction "NC_18") (pintype "no_connect"))
    )
    (net (code "88") (name "unconnected-(U2-NC-Pad19)") (class "Default")
      (node (ref "U2") (pin "19") (pinfunction "NC_19") (pintype "no_connect"))
    )
    (net (code "89") (name "unconnected-(U2-NC-Pad20)") (class "Default")
      (node (ref "U2") (pin "20") (pinfunction "NC_20") (pintype "no_connect"))
    )
    (net (code "90") (name "unconnected-(U2-NC-Pad21)") (class "Default")
      (node (ref "U2") (pin "21") (pinfunction "NC_21") (pintype "no_connect"))
    )
    (net (code "91") (name "unconnected-(U2-NC-Pad22)") (class "Default")
      (node (ref "U2") (pin "22") (pinfunction "NC_22") (pintype "no_connect"))
    )
    (net (code "92") (name "unconnected-(U2-NC1-Pad32)") (class "Default")
      (node (ref "U2") (pin "32") (pinfunction "NC1_32") (pintype "no_connect"))
    )
    (net (code "93") (name "unconnected-(U2-SENSOR_VN-Pad5)") (class "Default")
      (node (ref "U2") (pin "5") (pinfunction "SENSOR_VN_5") (pintype "input"))
    )
    (net (code "94") (name "unconnected-(U2-SENSOR_VP-Pad4)") (class "Default")
      (node (ref "U2") (pin "4") (pinfunction "SENSOR_VP_4") (pintype "input"))
    )
  )
)
